# 05_Inputs_28-35.net
KiCad netlist of a schematic drawn in Altium Designer
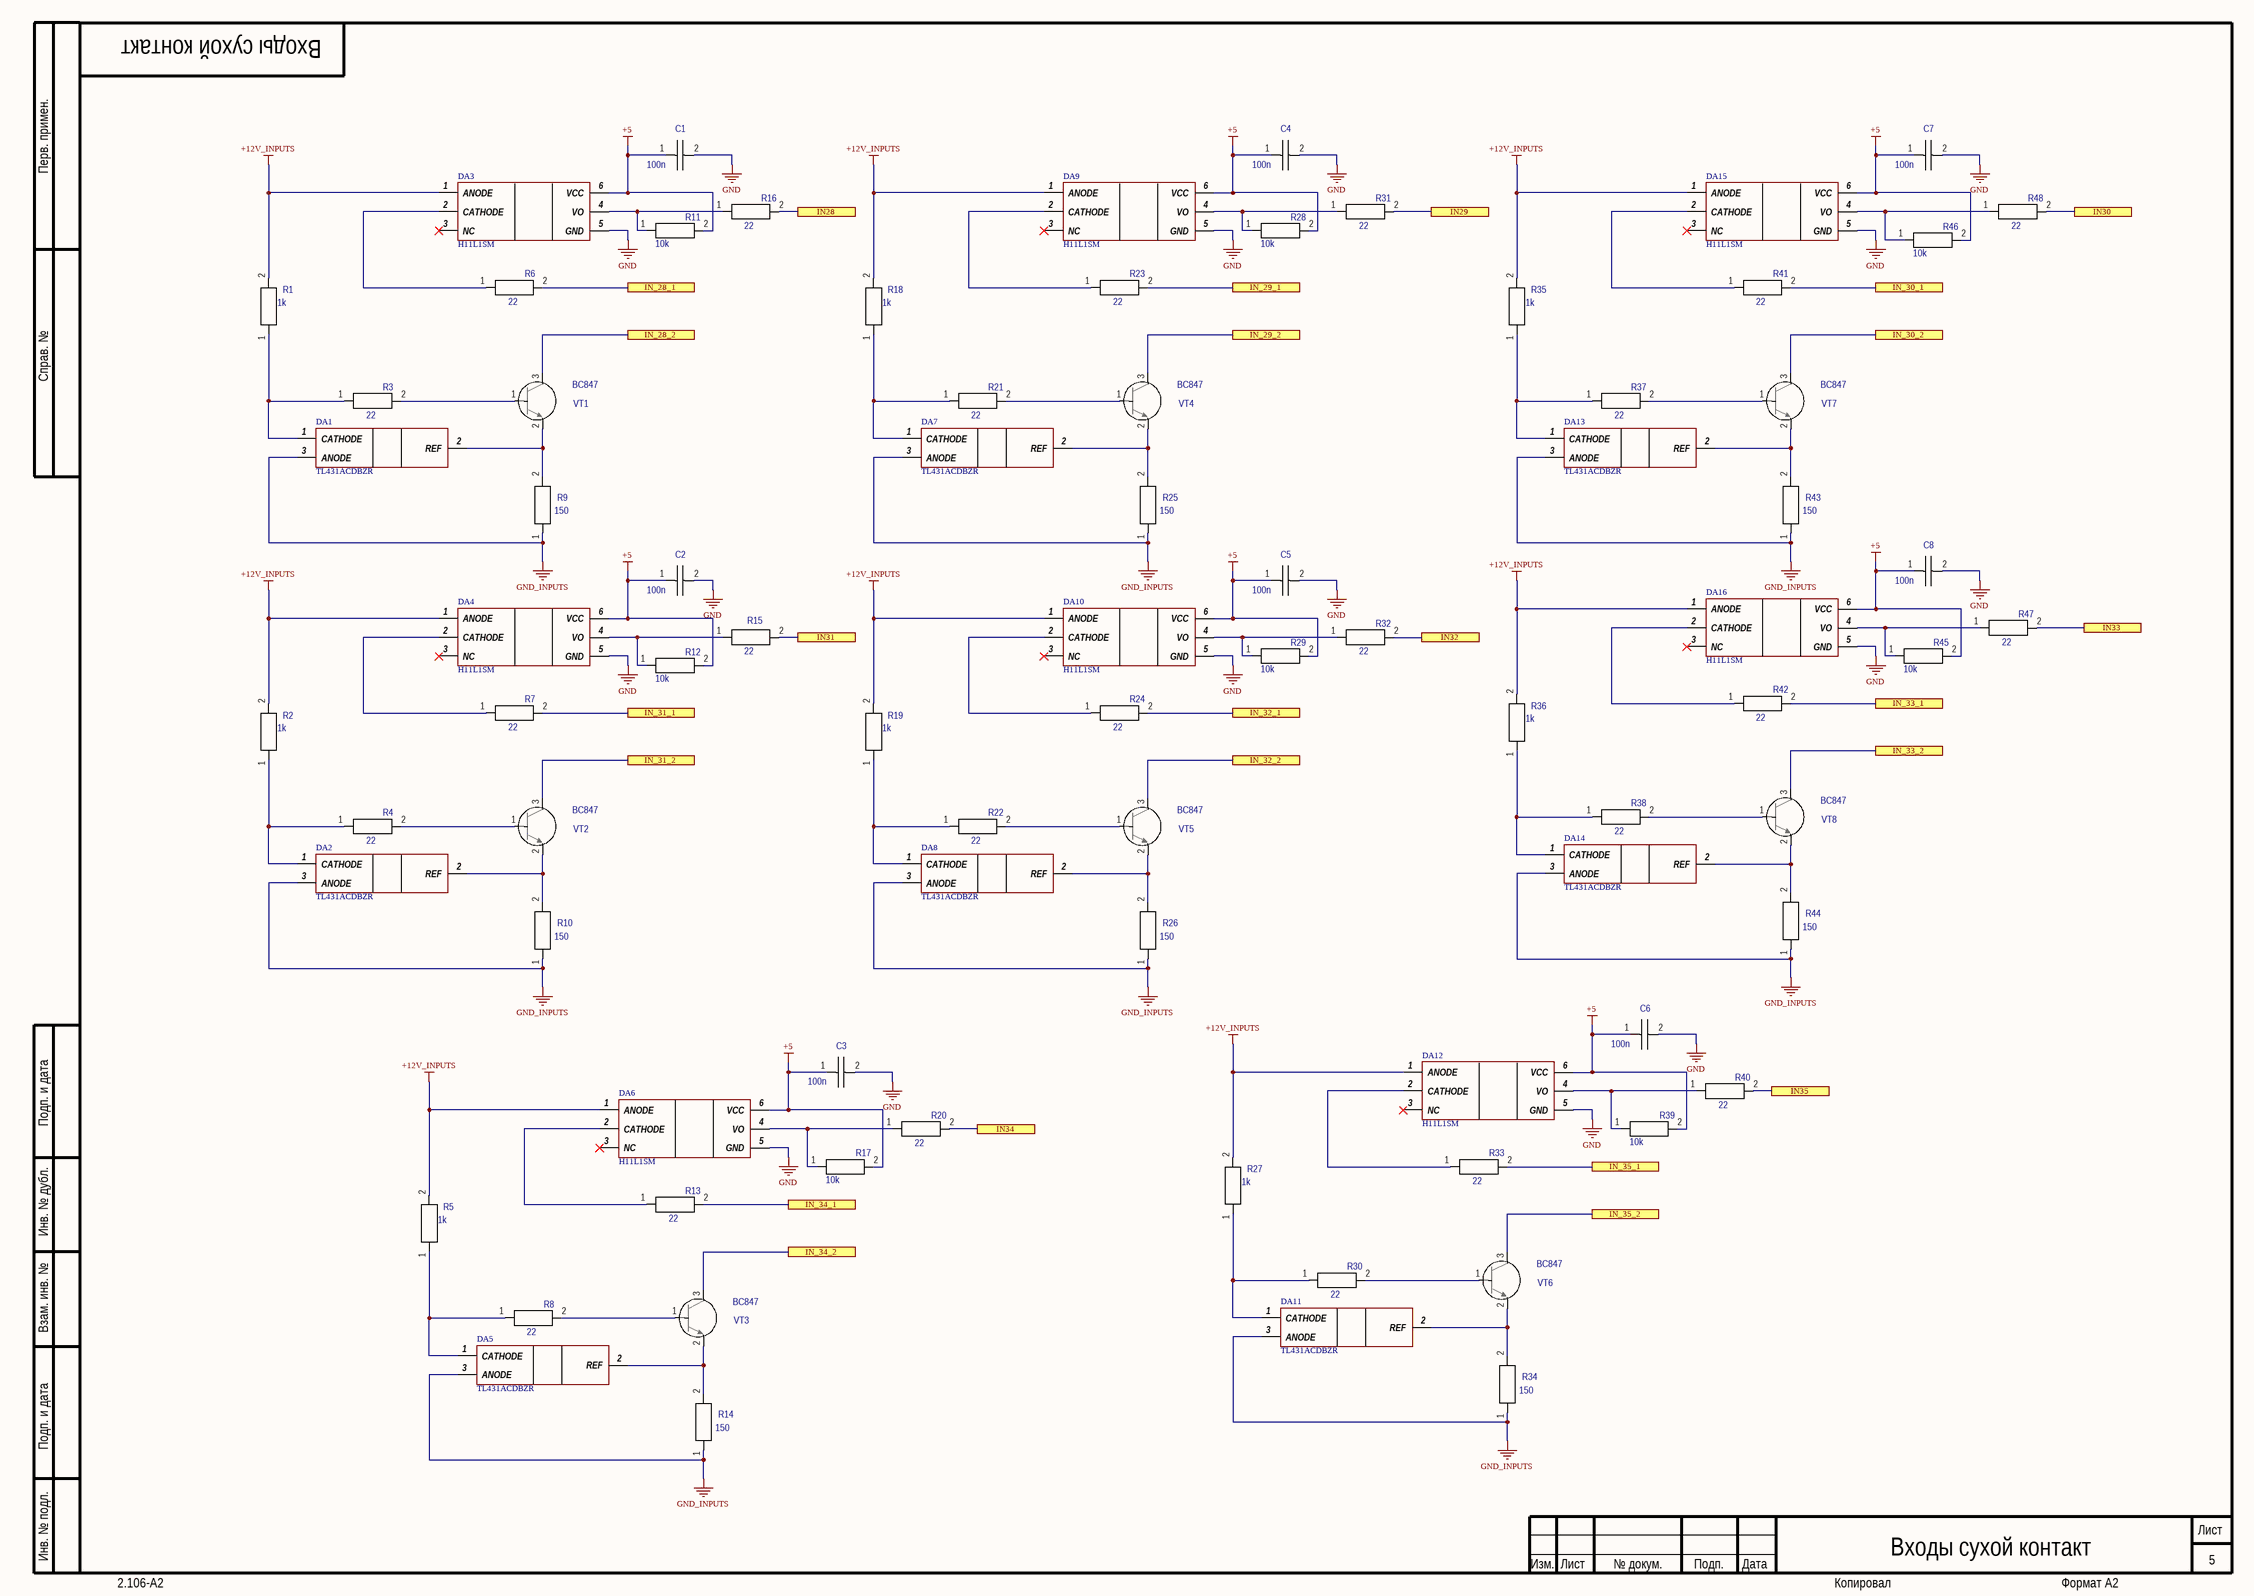
[diagram p0: 05_Inputs_28-35.SchDoc]

(export (version "E")
  (design (tool "Eeschema 10.0.6"))
  (components
    (comp (ref "C1")
      (value "100n")
      (footprint "C0603")
      (fields
        (field (name "PART NUMBER") "GRM188R71C104KA01D")
        (field (name "TOLERANCE") "±10%")
        (field (name "MANUFACTURER") "Murata Manufacturing")
      )
      (libsource (lib "AccessLibrary") (part "Capacitor"))
    )
    (comp (ref "C2")
      (value "100n")
      (footprint "C0603")
      (fields
        (field (name "PART NUMBER") "GRM188R71C104KA01D")
        (field (name "TOLERANCE") "±10%")
        (field (name "MANUFACTURER") "Murata Manufacturing")
      )
      (libsource (lib "AccessLibrary") (part "Capacitor"))
    )
    (comp (ref "C3")
      (value "100n")
      (footprint "C0603")
      (fields
        (field (name "PART NUMBER") "GRM188R71C104KA01D")
        (field (name "TOLERANCE") "±10%")
        (field (name "MANUFACTURER") "Murata Manufacturing")
      )
      (libsource (lib "AccessLibrary") (part "Capacitor"))
    )
    (comp (ref "C4")
      (value "100n")
      (footprint "C0603")
      (fields
        (field (name "PART NUMBER") "GRM188R71C104KA01D")
        (field (name "TOLERANCE") "±10%")
        (field (name "MANUFACTURER") "Murata Manufacturing")
      )
      (libsource (lib "AccessLibrary") (part "Capacitor"))
    )
    (comp (ref "C5")
      (value "100n")
      (footprint "C0603")
      (fields
        (field (name "PART NUMBER") "GRM188R71C104KA01D")
        (field (name "TOLERANCE") "±10%")
        (field (name "MANUFACTURER") "Murata Manufacturing")
      )
      (libsource (lib "AccessLibrary") (part "Capacitor"))
    )
    (comp (ref "C6")
      (value "100n")
      (footprint "C0603")
      (fields
        (field (name "PART NUMBER") "GRM188R71C104KA01D")
        (field (name "TOLERANCE") "±10%")
        (field (name "MANUFACTURER") "Murata Manufacturing")
      )
      (libsource (lib "AccessLibrary") (part "Capacitor"))
    )
    (comp (ref "C7")
      (value "100n")
      (footprint "C0603")
      (fields
        (field (name "PART NUMBER") "GRM188R71C104KA01D")
        (field (name "TOLERANCE") "±10%")
        (field (name "MANUFACTURER") "Murata Manufacturing")
      )
      (libsource (lib "AccessLibrary") (part "Capacitor"))
    )
    (comp (ref "C8")
      (value "100n")
      (footprint "C0603")
      (fields
        (field (name "PART NUMBER") "GRM188R71C104KA01D")
        (field (name "TOLERANCE") "±10%")
        (field (name "MANUFACTURER") "Murata Manufacturing")
      )
      (libsource (lib "AccessLibrary") (part "Capacitor"))
    )
    (comp (ref "DA1")
      (value "TL431ACDBZR")
      (footprint "board:SOT95P237X112-3N")
      (description "Integrated Circuit")
      (fields (field (name "MOUSER PART NUMBER") "595-TL431ACDBZR"))
      (libsource (lib "board") (part "TL431ACDBZR"))
    )
    (comp (ref "DA2")
      (value "TL431ACDBZR")
      (footprint "board:SOT95P237X112-3N")
      (description "Integrated Circuit")
      (fields (field (name "MOUSER PART NUMBER") "595-TL431ACDBZR"))
      (libsource (lib "board") (part "TL431ACDBZR"))
    )
    (comp (ref "DA3")
      (value "H11L1SM")
      (footprint "board:SOP254P1030X460-6N")
      (description "Integrated Circuit")
      (libsource (lib "board") (part "H11L1SM"))
    )
    (comp (ref "DA4")
      (value "H11L1SM")
      (footprint "board:SOP254P1030X460-6N")
      (description "Integrated Circuit")
      (libsource (lib "board") (part "H11L1SM"))
    )
    (comp (ref "DA5")
      (value "TL431ACDBZR")
      (footprint "board:SOT95P237X112-3N")
      (description "Integrated Circuit")
      (fields (field (name "MOUSER PART NUMBER") "595-TL431ACDBZR"))
      (libsource (lib "board") (part "TL431ACDBZR"))
    )
    (comp (ref "DA6")
      (value "H11L1SM")
      (footprint "board:SOP254P1030X460-6N")
      (description "Integrated Circuit")
      (libsource (lib "board") (part "H11L1SM"))
    )
    (comp (ref "DA7")
      (value "TL431ACDBZR")
      (footprint "board:SOT95P237X112-3N")
      (description "Integrated Circuit")
      (fields (field (name "MOUSER PART NUMBER") "595-TL431ACDBZR"))
      (libsource (lib "board") (part "TL431ACDBZR"))
    )
    (comp (ref "DA8")
      (value "TL431ACDBZR")
      (footprint "board:SOT95P237X112-3N")
      (description "Integrated Circuit")
      (fields (field (name "MOUSER PART NUMBER") "595-TL431ACDBZR"))
      (libsource (lib "board") (part "TL431ACDBZR"))
    )
    (comp (ref "DA9")
      (value "H11L1SM")
      (footprint "board:SOP254P1030X460-6N")
      (description "Integrated Circuit")
      (libsource (lib "board") (part "H11L1SM"))
    )
    (comp (ref "DA10")
      (value "H11L1SM")
      (footprint "board:SOP254P1030X460-6N")
      (description "Integrated Circuit")
      (libsource (lib "board") (part "H11L1SM"))
    )
    (comp (ref "DA11")
      (value "TL431ACDBZR")
      (footprint "board:SOT95P237X112-3N")
      (description "Integrated Circuit")
      (fields (field (name "MOUSER PART NUMBER") "595-TL431ACDBZR"))
      (libsource (lib "board") (part "TL431ACDBZR"))
    )
    (comp (ref "DA12")
      (value "H11L1SM")
      (footprint "board:SOP254P1030X460-6N")
      (description "Integrated Circuit")
      (libsource (lib "board") (part "H11L1SM"))
    )
    (comp (ref "DA13")
      (value "TL431ACDBZR")
      (footprint "board:SOT95P237X112-3N")
      (description "Integrated Circuit")
      (fields (field (name "MOUSER PART NUMBER") "595-TL431ACDBZR"))
      (libsource (lib "board") (part "TL431ACDBZR"))
    )
    (comp (ref "DA14")
      (value "TL431ACDBZR")
      (footprint "board:SOT95P237X112-3N")
      (description "Integrated Circuit")
      (fields (field (name "MOUSER PART NUMBER") "595-TL431ACDBZR"))
      (libsource (lib "board") (part "TL431ACDBZR"))
    )
    (comp (ref "DA15")
      (value "H11L1SM")
      (footprint "board:SOP254P1030X460-6N")
      (description "Integrated Circuit")
      (libsource (lib "board") (part "H11L1SM"))
    )
    (comp (ref "DA16")
      (value "H11L1SM")
      (footprint "board:SOP254P1030X460-6N")
      (description "Integrated Circuit")
      (libsource (lib "board") (part "H11L1SM"))
    )
    (comp (ref "R1")
      (value "1k")
      (footprint "RESC1608N")
      (fields
        (field (name "PART NUMBER") "RC0603FK-071KL")
        (field (name "TOLERANCE") "±1%")
        (field (name "MANUFACTURER") "Тайвань")
      )
      (libsource (lib "AccessLibrary") (part "Resistor"))
    )
    (comp (ref "R2")
      (value "1k")
      (footprint "RESC1608N")
      (fields
        (field (name "PART NUMBER") "RC0603FK-071KL")
        (field (name "TOLERANCE") "±1%")
        (field (name "MANUFACTURER") "Тайвань")
      )
      (libsource (lib "AccessLibrary") (part "Resistor"))
    )
    (comp (ref "R3")
      (value "22")
      (footprint "RESC1608N")
      (fields
        (field (name "PART NUMBER") "RC0603FK-0722RL")
        (field (name "TOLERANCE") "±1%")
        (field (name "MANUFACTURER") "Тайвань")
      )
      (libsource (lib "AccessLibrary") (part "Resistor"))
    )
    (comp (ref "R4")
      (value "22")
      (footprint "RESC1608N")
      (fields
        (field (name "PART NUMBER") "RC0603FK-0722RL")
        (field (name "TOLERANCE") "±1%")
        (field (name "MANUFACTURER") "Тайвань")
      )
      (libsource (lib "AccessLibrary") (part "Resistor"))
    )
    (comp (ref "R5")
      (value "1k")
      (footprint "RESC1608N")
      (fields
        (field (name "PART NUMBER") "RC0603FK-071KL")
        (field (name "TOLERANCE") "±1%")
        (field (name "MANUFACTURER") "Тайвань")
      )
      (libsource (lib "AccessLibrary") (part "Resistor"))
    )
    (comp (ref "R6")
      (value "22")
      (footprint "RESC1608N")
      (fields
        (field (name "PART NUMBER") "RC0603FK-0722RL")
        (field (name "TOLERANCE") "±1%")
        (field (name "MANUFACTURER") "Тайвань")
      )
      (libsource (lib "AccessLibrary") (part "Resistor"))
    )
    (comp (ref "R7")
      (value "22")
      (footprint "RESC1608N")
      (fields
        (field (name "PART NUMBER") "RC0603FK-0722RL")
        (field (name "TOLERANCE") "±1%")
        (field (name "MANUFACTURER") "Тайвань")
      )
      (libsource (lib "AccessLibrary") (part "Resistor"))
    )
    (comp (ref "R8")
      (value "22")
      (footprint "RESC1608N")
      (fields
        (field (name "PART NUMBER") "RC0603FK-0722RL")
        (field (name "TOLERANCE") "±1%")
        (field (name "MANUFACTURER") "Тайвань")
      )
      (libsource (lib "AccessLibrary") (part "Resistor"))
    )
    (comp (ref "R9")
      (value "150")
      (footprint "RESC1608N")
      (fields
        (field (name "PART NUMBER") "RC0603FK-07150RL")
        (field (name "TOLERANCE") "±1%")
        (field (name "MANUFACTURER") "Тайвань")
      )
      (libsource (lib "AccessLibrary") (part "Resistor"))
    )
    (comp (ref "R10")
      (value "150")
      (footprint "RESC1608N")
      (fields
        (field (name "PART NUMBER") "RC0603FK-07150RL")
        (field (name "TOLERANCE") "±1%")
        (field (name "MANUFACTURER") "Тайвань")
      )
      (libsource (lib "AccessLibrary") (part "Resistor"))
    )
    (comp (ref "R11")
      (value "10k")
      (footprint "RESC1608N")
      (fields
        (field (name "PART NUMBER") "RC0603FR-0710KL")
        (field (name "TOLERANCE") "±1%")
        (field (name "MANUFACTURER") "Тайвань")
      )
      (libsource (lib "AccessLibrary") (part "Resistor"))
    )
    (comp (ref "R12")
      (value "10k")
      (footprint "RESC1608N")
      (fields
        (field (name "PART NUMBER") "RC0603FR-0710KL")
        (field (name "TOLERANCE") "±1%")
        (field (name "MANUFACTURER") "Тайвань")
      )
      (libsource (lib "AccessLibrary") (part "Resistor"))
    )
    (comp (ref "R13")
      (value "22")
      (footprint "RESC1608N")
      (fields
        (field (name "PART NUMBER") "RC0603FK-0722RL")
        (field (name "TOLERANCE") "±1%")
        (field (name "MANUFACTURER") "Тайвань")
      )
      (libsource (lib "AccessLibrary") (part "Resistor"))
    )
    (comp (ref "R14")
      (value "150")
      (footprint "RESC1608N")
      (fields
        (field (name "PART NUMBER") "RC0603FK-07150RL")
        (field (name "TOLERANCE") "±1%")
        (field (name "MANUFACTURER") "Тайвань")
      )
      (libsource (lib "AccessLibrary") (part "Resistor"))
    )
    (comp (ref "R15")
      (value "22")
      (footprint "RESC1608N")
      (fields
        (field (name "PART NUMBER") "RC0603FK-0722RL")
        (field (name "TOLERANCE") "±1%")
        (field (name "MANUFACTURER") "Тайвань")
      )
      (libsource (lib "AccessLibrary") (part "Resistor"))
    )
    (comp (ref "R16")
      (value "22")
      (footprint "RESC1608N")
      (fields
        (field (name "PART NUMBER") "RC0603FK-0722RL")
        (field (name "TOLERANCE") "±1%")
        (field (name "MANUFACTURER") "Тайвань")
      )
      (libsource (lib "AccessLibrary") (part "Resistor"))
    )
    (comp (ref "R17")
      (value "10k")
      (footprint "RESC1608N")
      (fields
        (field (name "PART NUMBER") "RC0603FR-0710KL")
        (field (name "TOLERANCE") "±1%")
        (field (name "MANUFACTURER") "Тайвань")
      )
      (libsource (lib "AccessLibrary") (part "Resistor"))
    )
    (comp (ref "R18")
      (value "1k")
      (footprint "RESC1608N")
      (fields
        (field (name "PART NUMBER") "RC0603FK-071KL")
        (field (name "TOLERANCE") "±1%")
        (field (name "MANUFACTURER") "Тайвань")
      )
      (libsource (lib "AccessLibrary") (part "Resistor"))
    )
    (comp (ref "R19")
      (value "1k")
      (footprint "RESC1608N")
      (fields
        (field (name "PART NUMBER") "RC0603FK-071KL")
        (field (name "TOLERANCE") "±1%")
        (field (name "MANUFACTURER") "Тайвань")
      )
      (libsource (lib "AccessLibrary") (part "Resistor"))
    )
    (comp (ref "R20")
      (value "22")
      (footprint "RESC1608N")
      (fields
        (field (name "PART NUMBER") "RC0603FK-0722RL")
        (field (name "TOLERANCE") "±1%")
        (field (name "MANUFACTURER") "Тайвань")
      )
      (libsource (lib "AccessLibrary") (part "Resistor"))
    )
    (comp (ref "R21")
      (value "22")
      (footprint "RESC1608N")
      (fields
        (field (name "PART NUMBER") "RC0603FK-0722RL")
        (field (name "TOLERANCE") "±1%")
        (field (name "MANUFACTURER") "Тайвань")
      )
      (libsource (lib "AccessLibrary") (part "Resistor"))
    )
    (comp (ref "R22")
      (value "22")
      (footprint "RESC1608N")
      (fields
        (field (name "PART NUMBER") "RC0603FK-0722RL")
        (field (name "TOLERANCE") "±1%")
        (field (name "MANUFACTURER") "Тайвань")
      )
      (libsource (lib "AccessLibrary") (part "Resistor"))
    )
    (comp (ref "R23")
      (value "22")
      (footprint "RESC1608N")
      (fields
        (field (name "PART NUMBER") "RC0603FK-0722RL")
        (field (name "TOLERANCE") "±1%")
        (field (name "MANUFACTURER") "Тайвань")
      )
      (libsource (lib "AccessLibrary") (part "Resistor"))
    )
    (comp (ref "R24")
      (value "22")
      (footprint "RESC1608N")
      (fields
        (field (name "PART NUMBER") "RC0603FK-0722RL")
        (field (name "TOLERANCE") "±1%")
        (field (name "MANUFACTURER") "Тайвань")
      )
      (libsource (lib "AccessLibrary") (part "Resistor"))
    )
    (comp (ref "R25")
      (value "150")
      (footprint "RESC1608N")
      (fields
        (field (name "PART NUMBER") "RC0603FK-07150RL")
        (field (name "TOLERANCE") "±1%")
        (field (name "MANUFACTURER") "Тайвань")
      )
      (libsource (lib "AccessLibrary") (part "Resistor"))
    )
    (comp (ref "R26")
      (value "150")
      (footprint "RESC1608N")
      (fields
        (field (name "PART NUMBER") "RC0603FK-07150RL")
        (field (name "TOLERANCE") "±1%")
        (field (name "MANUFACTURER") "Тайвань")
      )
      (libsource (lib "AccessLibrary") (part "Resistor"))
    )
    (comp (ref "R27")
      (value "1k")
      (footprint "RESC1608N")
      (fields
        (field (name "PART NUMBER") "RC0603FK-071KL")
        (field (name "TOLERANCE") "±1%")
        (field (name "MANUFACTURER") "Тайвань")
      )
      (libsource (lib "AccessLibrary") (part "Resistor"))
    )
    (comp (ref "R28")
      (value "10k")
      (footprint "RESC1608N")
      (fields
        (field (name "PART NUMBER") "RC0603FR-0710KL")
        (field (name "TOLERANCE") "±1%")
        (field (name "MANUFACTURER") "Тайвань")
      )
      (libsource (lib "AccessLibrary") (part "Resistor"))
    )
    (comp (ref "R29")
      (value "10k")
      (footprint "RESC1608N")
      (fields
        (field (name "PART NUMBER") "RC0603FR-0710KL")
        (field (name "TOLERANCE") "±1%")
        (field (name "MANUFACTURER") "Тайвань")
      )
      (libsource (lib "AccessLibrary") (part "Resistor"))
    )
    (comp (ref "R30")
      (value "22")
      (footprint "RESC1608N")
      (fields
        (field (name "PART NUMBER") "RC0603FK-0722RL")
        (field (name "TOLERANCE") "±1%")
        (field (name "MANUFACTURER") "Тайвань")
      )
      (libsource (lib "AccessLibrary") (part "Resistor"))
    )
    (comp (ref "R31")
      (value "22")
      (footprint "RESC1608N")
      (fields
        (field (name "PART NUMBER") "RC0603FK-0722RL")
        (field (name "TOLERANCE") "±1%")
        (field (name "MANUFACTURER") "Тайвань")
      )
      (libsource (lib "AccessLibrary") (part "Resistor"))
    )
    (comp (ref "R32")
      (value "22")
      (footprint "RESC1608N")
      (fields
        (field (name "PART NUMBER") "RC0603FK-0722RL")
        (field (name "TOLERANCE") "±1%")
        (field (name "MANUFACTURER") "Тайвань")
      )
      (libsource (lib "AccessLibrary") (part "Resistor"))
    )
    (comp (ref "R33")
      (value "22")
      (footprint "RESC1608N")
      (fields
        (field (name "PART NUMBER") "RC0603FK-0722RL")
        (field (name "TOLERANCE") "±1%")
        (field (name "MANUFACTURER") "Тайвань")
      )
      (libsource (lib "AccessLibrary") (part "Resistor"))
    )
    (comp (ref "R34")
      (value "150")
      (footprint "RESC1608N")
      (fields
        (field (name "PART NUMBER") "RC0603FK-07150RL")
        (field (name "TOLERANCE") "±1%")
        (field (name "MANUFACTURER") "Тайвань")
      )
      (libsource (lib "AccessLibrary") (part "Resistor"))
    )
    (comp (ref "R35")
      (value "1k")
      (footprint "RESC1608N")
      (fields
        (field (name "PART NUMBER") "RC0603FK-071KL")
        (field (name "TOLERANCE") "±1%")
        (field (name "MANUFACTURER") "Тайвань")
      )
      (libsource (lib "AccessLibrary") (part "Resistor"))
    )
    (comp (ref "R36")
      (value "1k")
      (footprint "RESC1608N")
      (fields
        (field (name "PART NUMBER") "RC0603FK-071KL")
        (field (name "TOLERANCE") "±1%")
        (field (name "MANUFACTURER") "Тайвань")
      )
      (libsource (lib "AccessLibrary") (part "Resistor"))
    )
    (comp (ref "R37")
      (value "22")
      (footprint "RESC1608N")
      (fields
        (field (name "PART NUMBER") "RC0603FK-0722RL")
        (field (name "TOLERANCE") "±1%")
        (field (name "MANUFACTURER") "Тайвань")
      )
      (libsource (lib "AccessLibrary") (part "Resistor"))
    )
    (comp (ref "R38")
      (value "22")
      (footprint "RESC1608N")
      (fields
        (field (name "PART NUMBER") "RC0603FK-0722RL")
        (field (name "TOLERANCE") "±1%")
        (field (name "MANUFACTURER") "Тайвань")
      )
      (libsource (lib "AccessLibrary") (part "Resistor"))
    )
    (comp (ref "R39")
      (value "10k")
      (footprint "RESC1608N")
      (fields
        (field (name "PART NUMBER") "RC0603FR-0710KL")
        (field (name "TOLERANCE") "±1%")
        (field (name "MANUFACTURER") "Тайвань")
      )
      (libsource (lib "AccessLibrary") (part "Resistor"))
    )
    (comp (ref "R40")
      (value "22")
      (footprint "RESC1608N")
      (fields
        (field (name "PART NUMBER") "RC0603FK-0722RL")
        (field (name "TOLERANCE") "±1%")
        (field (name "MANUFACTURER") "Тайвань")
      )
      (libsource (lib "AccessLibrary") (part "Resistor"))
    )
    (comp (ref "R41")
      (value "22")
      (footprint "RESC1608N")
      (fields
        (field (name "PART NUMBER") "RC0603FK-0722RL")
        (field (name "TOLERANCE") "±1%")
        (field (name "MANUFACTURER") "Тайвань")
      )
      (libsource (lib "AccessLibrary") (part "Resistor"))
    )
    (comp (ref "R42")
      (value "22")
      (footprint "RESC1608N")
      (fields
        (field (name "PART NUMBER") "RC0603FK-0722RL")
        (field (name "TOLERANCE") "±1%")
        (field (name "MANUFACTURER") "Тайвань")
      )
      (libsource (lib "AccessLibrary") (part "Resistor"))
    )
    (comp (ref "R43")
      (value "150")
      (footprint "RESC1608N")
      (fields
        (field (name "PART NUMBER") "RC0603FK-07150RL")
        (field (name "TOLERANCE") "±1%")
        (field (name "MANUFACTURER") "Тайвань")
      )
      (libsource (lib "AccessLibrary") (part "Resistor"))
    )
    (comp (ref "R44")
      (value "150")
      (footprint "RESC1608N")
      (fields
        (field (name "PART NUMBER") "RC0603FK-07150RL")
        (field (name "TOLERANCE") "±1%")
        (field (name "MANUFACTURER") "Тайвань")
      )
      (libsource (lib "AccessLibrary") (part "Resistor"))
    )
    (comp (ref "R45")
      (value "10k")
      (footprint "RESC1608N")
      (fields
        (field (name "PART NUMBER") "RC0603FR-0710KL")
        (field (name "TOLERANCE") "±1%")
        (field (name "MANUFACTURER") "Тайвань")
      )
      (libsource (lib "AccessLibrary") (part "Resistor"))
    )
    (comp (ref "R46")
      (value "10k")
      (footprint "RESC1608N")
      (fields
        (field (name "PART NUMBER") "RC0603FR-0710KL")
        (field (name "TOLERANCE") "±1%")
        (field (name "MANUFACTURER") "Тайвань")
      )
      (libsource (lib "AccessLibrary") (part "Resistor"))
    )
    (comp (ref "R47")
      (value "22")
      (footprint "RESC1608N")
      (fields
        (field (name "PART NUMBER") "RC0603FK-0722RL")
        (field (name "TOLERANCE") "±1%")
        (field (name "MANUFACTURER") "Тайвань")
      )
      (libsource (lib "AccessLibrary") (part "Resistor"))
    )
    (comp (ref "R48")
      (value "22")
      (footprint "RESC1608N")
      (fields
        (field (name "PART NUMBER") "RC0603FK-0722RL")
        (field (name "TOLERANCE") "±1%")
        (field (name "MANUFACTURER") "Тайвань")
      )
      (libsource (lib "AccessLibrary") (part "Resistor"))
    )
    (comp (ref "VT1")
      (value "BC847")
      (footprint "SOT23-3N")
      (fields (field (name "COM") "BC847") (field (name "MANUFACTURER") "NXP Semiconductor"))
      (libsource (lib "AccessLibrary") (part "Transistor_npn_1b-2e-3c"))
    )
    (comp (ref "VT2")
      (value "BC847")
      (footprint "SOT23-3N")
      (fields (field (name "COM") "BC847") (field (name "MANUFACTURER") "NXP Semiconductor"))
      (libsource (lib "AccessLibrary") (part "Transistor_npn_1b-2e-3c"))
    )
    (comp (ref "VT3")
      (value "BC847")
      (footprint "SOT23-3N")
      (fields (field (name "COM") "BC847") (field (name "MANUFACTURER") "NXP Semiconductor"))
      (libsource (lib "AccessLibrary") (part "Transistor_npn_1b-2e-3c"))
    )
    (comp (ref "VT4")
      (value "BC847")
      (footprint "SOT23-3N")
      (fields (field (name "COM") "BC847") (field (name "MANUFACTURER") "NXP Semiconductor"))
      (libsource (lib "AccessLibrary") (part "Transistor_npn_1b-2e-3c"))
    )
    (comp (ref "VT5")
      (value "BC847")
      (footprint "SOT23-3N")
      (fields (field (name "COM") "BC847") (field (name "MANUFACTURER") "NXP Semiconductor"))
      (libsource (lib "AccessLibrary") (part "Transistor_npn_1b-2e-3c"))
    )
    (comp (ref "VT6")
      (value "BC847")
      (footprint "SOT23-3N")
      (fields (field (name "COM") "BC847") (field (name "MANUFACTURER") "NXP Semiconductor"))
      (libsource (lib "AccessLibrary") (part "Transistor_npn_1b-2e-3c"))
    )
    (comp (ref "VT7")
      (value "BC847")
      (footprint "SOT23-3N")
      (fields (field (name "COM") "BC847") (field (name "MANUFACTURER") "NXP Semiconductor"))
      (libsource (lib "AccessLibrary") (part "Transistor_npn_1b-2e-3c"))
    )
    (comp (ref "VT8")
      (value "BC847")
      (footprint "SOT23-3N")
      (fields (field (name "COM") "BC847") (field (name "MANUFACTURER") "NXP Semiconductor"))
      (libsource (lib "AccessLibrary") (part "Transistor_npn_1b-2e-3c"))
    )
  )
  (nets
    (net (code "1") (name "+5") (class "Default")
      (node (ref "C1") (pin "1") (pinfunction "1_1") (pintype "passive"))
      (node (ref "C2") (pin "1") (pinfunction "1_1") (pintype "passive"))
      (node (ref "C3") (pin "1") (pinfunction "1_1") (pintype "passive"))
      (node (ref "C4") (pin "1") (pinfunction "1_1") (pintype "passive"))
      (node (ref "C5") (pin "1") (pinfunction "1_1") (pintype "passive"))
      (node (ref "C6") (pin "1") (pinfunction "1_1") (pintype "passive"))
      (node (ref "C7") (pin "1") (pinfunction "1_1") (pintype "passive"))
      (node (ref "C8") (pin "1") (pinfunction "1_1") (pintype "passive"))
      (node (ref "DA10") (pin "6") (pinfunction "VCC_6") (pintype "passive"))
      (node (ref "DA12") (pin "6") (pinfunction "VCC_6") (pintype "passive"))
      (node (ref "DA15") (pin "6") (pinfunction "VCC_6") (pintype "passive"))
      (node (ref "DA16") (pin "6") (pinfunction "VCC_6") (pintype "passive"))
      (node (ref "DA3") (pin "6") (pinfunction "VCC_6") (pintype "passive"))
      (node (ref "DA4") (pin "6") (pinfunction "VCC_6") (pintype "passive"))
      (node (ref "DA6") (pin "6") (pinfunction "VCC_6") (pintype "passive"))
      (node (ref "DA9") (pin "6") (pinfunction "VCC_6") (pintype "passive"))
      (node (ref "R11") (pin "2") (pinfunction "2_2") (pintype "passive"))
      (node (ref "R12") (pin "2") (pinfunction "2_2") (pintype "passive"))
      (node (ref "R17") (pin "2") (pinfunction "2_2") (pintype "passive"))
      (node (ref "R28") (pin "2") (pinfunction "2_2") (pintype "passive"))
      (node (ref "R29") (pin "2") (pinfunction "2_2") (pintype "passive"))
      (node (ref "R39") (pin "2") (pinfunction "2_2") (pintype "passive"))
      (node (ref "R45") (pin "2") (pinfunction "2_2") (pintype "passive"))
      (node (ref "R46") (pin "2") (pinfunction "2_2") (pintype "passive"))
    )
    (net (code "2") (name "+12V_INPUTS") (class "Default")
      (node (ref "DA10") (pin "1") (pinfunction "ANODE_1") (pintype "passive"))
      (node (ref "DA12") (pin "1") (pinfunction "ANODE_1") (pintype "passive"))
      (node (ref "DA15") (pin "1") (pinfunction "ANODE_1") (pintype "passive"))
      (node (ref "DA16") (pin "1") (pinfunction "ANODE_1") (pintype "passive"))
      (node (ref "DA3") (pin "1") (pinfunction "ANODE_1") (pintype "passive"))
      (node (ref "DA4") (pin "1") (pinfunction "ANODE_1") (pintype "passive"))
      (node (ref "DA6") (pin "1") (pinfunction "ANODE_1") (pintype "passive"))
      (node (ref "DA9") (pin "1") (pinfunction "ANODE_1") (pintype "passive"))
      (node (ref "R1") (pin "2") (pinfunction "2_2") (pintype "passive"))
      (node (ref "R18") (pin "2") (pinfunction "2_2") (pintype "passive"))
      (node (ref "R19") (pin "2") (pinfunction "2_2") (pintype "passive"))
      (node (ref "R2") (pin "2") (pinfunction "2_2") (pintype "passive"))
      (node (ref "R27") (pin "2") (pinfunction "2_2") (pintype "passive"))
      (node (ref "R35") (pin "2") (pinfunction "2_2") (pintype "passive"))
      (node (ref "R36") (pin "2") (pinfunction "2_2") (pintype "passive"))
      (node (ref "R5") (pin "2") (pinfunction "2_2") (pintype "passive"))
    )
    (net (code "3") (name "/IN28") (class "Default")
      (node (ref "R16") (pin "2") (pinfunction "2_2") (pintype "passive"))
    )
    (net (code "4") (name "/IN29") (class "Default")
      (node (ref "R31") (pin "2") (pinfunction "2_2") (pintype "passive"))
    )
    (net (code "5") (name "/IN30") (class "Default")
      (node (ref "R48") (pin "2") (pinfunction "2_2") (pintype "passive"))
    )
    (net (code "6") (name "/IN31") (class "Default")
      (node (ref "R15") (pin "2") (pinfunction "2_2") (pintype "passive"))
    )
    (net (code "7") (name "/IN32") (class "Default")
      (node (ref "R32") (pin "2") (pinfunction "2_2") (pintype "passive"))
    )
    (net (code "8") (name "/IN33") (class "Default")
      (node (ref "R47") (pin "2") (pinfunction "2_2") (pintype "passive"))
    )
    (net (code "9") (name "/IN34") (class "Default")
      (node (ref "R20") (pin "2") (pinfunction "2_2") (pintype "passive"))
    )
    (net (code "10") (name "/IN35") (class "Default")
      (node (ref "R40") (pin "2") (pinfunction "2_2") (pintype "passive"))
    )
    (net (code "11") (name "/IN_28_1") (class "Default")
      (node (ref "R6") (pin "2") (pinfunction "2_2") (pintype "passive"))
    )
    (net (code "12") (name "/IN_28_2") (class "Default")
      (node (ref "VT1") (pin "3") (pinfunction "3_3") (pintype "passive"))
    )
    (net (code "13") (name "/IN_29_1") (class "Default")
      (node (ref "R23") (pin "2") (pinfunction "2_2") (pintype "passive"))
    )
    (net (code "14") (name "/IN_29_2") (class "Default")
      (node (ref "VT4") (pin "3") (pinfunction "3_3") (pintype "passive"))
    )
    (net (code "15") (name "/IN_30_1") (class "Default")
      (node (ref "R41") (pin "2") (pinfunction "2_2") (pintype "passive"))
    )
    (net (code "16") (name "/IN_30_2") (class "Default")
      (node (ref "VT7") (pin "3") (pinfunction "3_3") (pintype "passive"))
    )
    (net (code "17") (name "/IN_31_1") (class "Default")
      (node (ref "R7") (pin "2") (pinfunction "2_2") (pintype "passive"))
    )
    (net (code "18") (name "/IN_31_2") (class "Default")
      (node (ref "VT2") (pin "3") (pinfunction "3_3") (pintype "passive"))
    )
    (net (code "19") (name "/IN_32_1") (class "Default")
      (node (ref "R24") (pin "2") (pinfunction "2_2") (pintype "passive"))
    )
    (net (code "20") (name "/IN_32_2") (class "Default")
      (node (ref "VT5") (pin "3") (pinfunction "3_3") (pintype "passive"))
    )
    (net (code "21") (name "/IN_33_1") (class "Default")
      (node (ref "R42") (pin "2") (pinfunction "2_2") (pintype "passive"))
    )
    (net (code "22") (name "/IN_33_2") (class "Default")
      (node (ref "VT8") (pin "3") (pinfunction "3_3") (pintype "passive"))
    )
    (net (code "23") (name "/IN_34_1") (class "Default")
      (node (ref "R13") (pin "2") (pinfunction "2_2") (pintype "passive"))
    )
    (net (code "24") (name "/IN_34_2") (class "Default")
      (node (ref "VT3") (pin "3") (pinfunction "3_3") (pintype "passive"))
    )
    (net (code "25") (name "/IN_35_1") (class "Default")
      (node (ref "R33") (pin "2") (pinfunction "2_2") (pintype "passive"))
    )
    (net (code "26") (name "/IN_35_2") (class "Default")
      (node (ref "VT6") (pin "3") (pinfunction "3_3") (pintype "passive"))
    )
    (net (code "27") (name "GND") (class "Default")
      (node (ref "C1") (pin "2") (pinfunction "2_2") (pintype "passive"))
      (node (ref "C2") (pin "2") (pinfunction "2_2") (pintype "passive"))
      (node (ref "C3") (pin "2") (pinfunction "2_2") (pintype "passive"))
      (node (ref "C4") (pin "2") (pinfunction "2_2") (pintype "passive"))
      (node (ref "C5") (pin "2") (pinfunction "2_2") (pintype "passive"))
      (node (ref "C6") (pin "2") (pinfunction "2_2") (pintype "passive"))
      (node (ref "C7") (pin "2") (pinfunction "2_2") (pintype "passive"))
      (node (ref "C8") (pin "2") (pinfunction "2_2") (pintype "passive"))
      (node (ref "DA10") (pin "5") (pinfunction "GND_5") (pintype "passive"))
      (node (ref "DA12") (pin "5") (pinfunction "GND_5") (pintype "passive"))
      (node (ref "DA15") (pin "5") (pinfunction "GND_5") (pintype "passive"))
      (node (ref "DA16") (pin "5") (pinfunction "GND_5") (pintype "passive"))
      (node (ref "DA3") (pin "5") (pinfunction "GND_5") (pintype "passive"))
      (node (ref "DA4") (pin "5") (pinfunction "GND_5") (pintype "passive"))
      (node (ref "DA6") (pin "5") (pinfunction "GND_5") (pintype "passive"))
      (node (ref "DA9") (pin "5") (pinfunction "GND_5") (pintype "passive"))
    )
    (net (code "28") (name "GND_INPUTS") (class "Default")
      (node (ref "DA1") (pin "3") (pinfunction "ANODE_3") (pintype "passive"))
      (node (ref "DA11") (pin "3") (pinfunction "ANODE_3") (pintype "passive"))
      (node (ref "DA13") (pin "3") (pinfunction "ANODE_3") (pintype "passive"))
      (node (ref "DA14") (pin "3") (pinfunction "ANODE_3") (pintype "passive"))
      (node (ref "DA2") (pin "3") (pinfunction "ANODE_3") (pintype "passive"))
      (node (ref "DA5") (pin "3") (pinfunction "ANODE_3") (pintype "passive"))
      (node (ref "DA7") (pin "3") (pinfunction "ANODE_3") (pintype "passive"))
      (node (ref "DA8") (pin "3") (pinfunction "ANODE_3") (pintype "passive"))
      (node (ref "R10") (pin "1") (pinfunction "1_1") (pintype "passive"))
      (node (ref "R14") (pin "1") (pinfunction "1_1") (pintype "passive"))
      (node (ref "R25") (pin "1") (pinfunction "1_1") (pintype "passive"))
      (node (ref "R26") (pin "1") (pinfunction "1_1") (pintype "passive"))
      (node (ref "R34") (pin "1") (pinfunction "1_1") (pintype "passive"))
      (node (ref "R43") (pin "1") (pinfunction "1_1") (pintype "passive"))
      (node (ref "R44") (pin "1") (pinfunction "1_1") (pintype "passive"))
      (node (ref "R9") (pin "1") (pinfunction "1_1") (pintype "passive"))
    )
    (net (code "29") (name "Net-(DA1-CATHODE)") (class "Default")
      (node (ref "DA1") (pin "1") (pinfunction "CATHODE_1") (pintype "passive"))
      (node (ref "R1") (pin "1") (pinfunction "1_1") (pintype "passive"))
      (node (ref "R3") (pin "1") (pinfunction "1_1") (pintype "passive"))
    )
    (net (code "30") (name "Net-(DA1-REF)") (class "Default")
      (node (ref "DA1") (pin "2") (pinfunction "REF_2") (pintype "passive"))
      (node (ref "R9") (pin "2") (pinfunction "2_2") (pintype "passive"))
      (node (ref "VT1") (pin "2") (pinfunction "2_2") (pintype "passive"))
    )
    (net (code "31") (name "Net-(DA2-CATHODE)") (class "Default")
      (node (ref "DA2") (pin "1") (pinfunction "CATHODE_1") (pintype "passive"))
      (node (ref "R2") (pin "1") (pinfunction "1_1") (pintype "passive"))
      (node (ref "R4") (pin "1") (pinfunction "1_1") (pintype "passive"))
    )
    (net (code "32") (name "Net-(DA2-REF)") (class "Default")
      (node (ref "DA2") (pin "2") (pinfunction "REF_2") (pintype "passive"))
      (node (ref "R10") (pin "2") (pinfunction "2_2") (pintype "passive"))
      (node (ref "VT2") (pin "2") (pinfunction "2_2") (pintype "passive"))
    )
    (net (code "33") (name "Net-(DA3-CATHODE)") (class "Default")
      (node (ref "DA3") (pin "2") (pinfunction "CATHODE_2") (pintype "passive"))
      (node (ref "R6") (pin "1") (pinfunction "1_1") (pintype "passive"))
    )
    (net (code "34") (name "Net-(DA3-VO)") (class "Default")
      (node (ref "DA3") (pin "4") (pinfunction "VO_4") (pintype "passive"))
      (node (ref "R11") (pin "1") (pinfunction "1_1") (pintype "passive"))
      (node (ref "R16") (pin "1") (pinfunction "1_1") (pintype "passive"))
    )
    (net (code "35") (name "Net-(DA4-CATHODE)") (class "Default")
      (node (ref "DA4") (pin "2") (pinfunction "CATHODE_2") (pintype "passive"))
      (node (ref "R7") (pin "1") (pinfunction "1_1") (pintype "passive"))
    )
    (net (code "36") (name "Net-(DA4-VO)") (class "Default")
      (node (ref "DA4") (pin "4") (pinfunction "VO_4") (pintype "passive"))
      (node (ref "R12") (pin "1") (pinfunction "1_1") (pintype "passive"))
      (node (ref "R15") (pin "1") (pinfunction "1_1") (pintype "passive"))
    )
    (net (code "37") (name "Net-(DA5-CATHODE)") (class "Default")
      (node (ref "DA5") (pin "1") (pinfunction "CATHODE_1") (pintype "passive"))
      (node (ref "R5") (pin "1") (pinfunction "1_1") (pintype "passive"))
      (node (ref "R8") (pin "1") (pinfunction "1_1") (pintype "passive"))
    )
    (net (code "38") (name "Net-(DA5-REF)") (class "Default")
      (node (ref "DA5") (pin "2") (pinfunction "REF_2") (pintype "passive"))
      (node (ref "R14") (pin "2") (pinfunction "2_2") (pintype "passive"))
      (node (ref "VT3") (pin "2") (pinfunction "2_2") (pintype "passive"))
    )
    (net (code "39") (name "Net-(DA6-CATHODE)") (class "Default")
      (node (ref "DA6") (pin "2") (pinfunction "CATHODE_2") (pintype "passive"))
      (node (ref "R13") (pin "1") (pinfunction "1_1") (pintype "passive"))
    )
    (net (code "40") (name "Net-(DA6-VO)") (class "Default")
      (node (ref "DA6") (pin "4") (pinfunction "VO_4") (pintype "passive"))
      (node (ref "R17") (pin "1") (pinfunction "1_1") (pintype "passive"))
      (node (ref "R20") (pin "1") (pinfunction "1_1") (pintype "passive"))
    )
    (net (code "41") (name "Net-(DA7-CATHODE)") (class "Default")
      (node (ref "DA7") (pin "1") (pinfunction "CATHODE_1") (pintype "passive"))
      (node (ref "R18") (pin "1") (pinfunction "1_1") (pintype "passive"))
      (node (ref "R21") (pin "1") (pinfunction "1_1") (pintype "passive"))
    )
    (net (code "42") (name "Net-(DA7-REF)") (class "Default")
      (node (ref "DA7") (pin "2") (pinfunction "REF_2") (pintype "passive"))
      (node (ref "R25") (pin "2") (pinfunction "2_2") (pintype "passive"))
      (node (ref "VT4") (pin "2") (pinfunction "2_2") (pintype "passive"))
    )
    (net (code "43") (name "Net-(DA8-CATHODE)") (class "Default")
      (node (ref "DA8") (pin "1") (pinfunction "CATHODE_1") (pintype "passive"))
      (node (ref "R19") (pin "1") (pinfunction "1_1") (pintype "passive"))
      (node (ref "R22") (pin "1") (pinfunction "1_1") (pintype "passive"))
    )
    (net (code "44") (name "Net-(DA8-REF)") (class "Default")
      (node (ref "DA8") (pin "2") (pinfunction "REF_2") (pintype "passive"))
      (node (ref "R26") (pin "2") (pinfunction "2_2") (pintype "passive"))
      (node (ref "VT5") (pin "2") (pinfunction "2_2") (pintype "passive"))
    )
    (net (code "45") (name "Net-(DA9-CATHODE)") (class "Default")
      (node (ref "DA9") (pin "2") (pinfunction "CATHODE_2") (pintype "passive"))
      (node (ref "R23") (pin "1") (pinfunction "1_1") (pintype "passive"))
    )
    (net (code "46") (name "Net-(DA9-VO)") (class "Default")
      (node (ref "DA9") (pin "4") (pinfunction "VO_4") (pintype "passive"))
      (node (ref "R28") (pin "1") (pinfunction "1_1") (pintype "passive"))
      (node (ref "R31") (pin "1") (pinfunction "1_1") (pintype "passive"))
    )
    (net (code "47") (name "Net-(DA10-CATHODE)") (class "Default")
      (node (ref "DA10") (pin "2") (pinfunction "CATHODE_2") (pintype "passive"))
      (node (ref "R24") (pin "1") (pinfunction "1_1") (pintype "passive"))
    )
    (net (code "48") (name "Net-(DA10-VO)") (class "Default")
      (node (ref "DA10") (pin "4") (pinfunction "VO_4") (pintype "passive"))
      (node (ref "R29") (pin "1") (pinfunction "1_1") (pintype "passive"))
      (node (ref "R32") (pin "1") (pinfunction "1_1") (pintype "passive"))
    )
    (net (code "49") (name "Net-(DA11-CATHODE)") (class "Default")
      (node (ref "DA11") (pin "1") (pinfunction "CATHODE_1") (pintype "passive"))
      (node (ref "R27") (pin "1") (pinfunction "1_1") (pintype "passive"))
      (node (ref "R30") (pin "1") (pinfunction "1_1") (pintype "passive"))
    )
    (net (code "50") (name "Net-(DA11-REF)") (class "Default")
      (node (ref "DA11") (pin "2") (pinfunction "REF_2") (pintype "passive"))
      (node (ref "R34") (pin "2") (pinfunction "2_2") (pintype "passive"))
      (node (ref "VT6") (pin "2") (pinfunction "2_2") (pintype "passive"))
    )
    (net (code "51") (name "Net-(DA12-CATHODE)") (class "Default")
      (node (ref "DA12") (pin "2") (pinfunction "CATHODE_2") (pintype "passive"))
      (node (ref "R33") (pin "1") (pinfunction "1_1") (pintype "passive"))
    )
    (net (code "52") (name "Net-(DA12-VO)") (class "Default")
      (node (ref "DA12") (pin "4") (pinfunction "VO_4") (pintype "passive"))
      (node (ref "R39") (pin "1") (pinfunction "1_1") (pintype "passive"))
      (node (ref "R40") (pin "1") (pinfunction "1_1") (pintype "passive"))
    )
    (net (code "53") (name "Net-(DA13-CATHODE)") (class "Default")
      (node (ref "DA13") (pin "1") (pinfunction "CATHODE_1") (pintype "passive"))
      (node (ref "R35") (pin "1") (pinfunction "1_1") (pintype "passive"))
      (node (ref "R37") (pin "1") (pinfunction "1_1") (pintype "passive"))
    )
    (net (code "54") (name "Net-(DA13-REF)") (class "Default")
      (node (ref "DA13") (pin "2") (pinfunction "REF_2") (pintype "passive"))
      (node (ref "R43") (pin "2") (pinfunction "2_2") (pintype "passive"))
      (node (ref "VT7") (pin "2") (pinfunction "2_2") (pintype "passive"))
    )
    (net (code "55") (name "Net-(DA14-CATHODE)") (class "Default")
      (node (ref "DA14") (pin "1") (pinfunction "CATHODE_1") (pintype "passive"))
      (node (ref "R36") (pin "1") (pinfunction "1_1") (pintype "passive"))
      (node (ref "R38") (pin "1") (pinfunction "1_1") (pintype "passive"))
    )
    (net (code "56") (name "Net-(DA14-REF)") (class "Default")
      (node (ref "DA14") (pin "2") (pinfunction "REF_2") (pintype "passive"))
      (node (ref "R44") (pin "2") (pinfunction "2_2") (pintype "passive"))
      (node (ref "VT8") (pin "2") (pinfunction "2_2") (pintype "passive"))
    )
    (net (code "57") (name "Net-(DA15-CATHODE)") (class "Default")
      (node (ref "DA15") (pin "2") (pinfunction "CATHODE_2") (pintype "passive"))
      (node (ref "R41") (pin "1") (pinfunction "1_1") (pintype "passive"))
    )
    (net (code "58") (name "Net-(DA15-VO)") (class "Default")
      (node (ref "DA15") (pin "4") (pinfunction "VO_4") (pintype "passive"))
      (node (ref "R46") (pin "1") (pinfunction "1_1") (pintype "passive"))
      (node (ref "R48") (pin "1") (pinfunction "1_1") (pintype "passive"))
    )
    (net (code "59") (name "Net-(DA16-CATHODE)") (class "Default")
      (node (ref "DA16") (pin "2") (pinfunction "CATHODE_2") (pintype "passive"))
      (node (ref "R42") (pin "1") (pinfunction "1_1") (pintype "passive"))
    )
    (net (code "60") (name "Net-(DA16-VO)") (class "Default")
      (node (ref "DA16") (pin "4") (pinfunction "VO_4") (pintype "passive"))
      (node (ref "R45") (pin "1") (pinfunction "1_1") (pintype "passive"))
      (node (ref "R47") (pin "1") (pinfunction "1_1") (pintype "passive"))
    )
    (net (code "61") (name "Net-(R3-Pad2)") (class "Default")
      (node (ref "R3") (pin "2") (pinfunction "2_2") (pintype "passive"))
      (node (ref "VT1") (pin "1") (pinfunction "1_1") (pintype "passive"))
    )
    (net (code "62") (name "Net-(R4-Pad2)") (class "Default")
      (node (ref "R4") (pin "2") (pinfunction "2_2") (pintype "passive"))
      (node (ref "VT2") (pin "1") (pinfunction "1_1") (pintype "passive"))
    )
    (net (code "63") (name "Net-(R8-Pad2)") (class "Default")
      (node (ref "R8") (pin "2") (pinfunction "2_2") (pintype "passive"))
      (node (ref "VT3") (pin "1") (pinfunction "1_1") (pintype "passive"))
    )
    (net (code "64") (name "Net-(R21-Pad2)") (class "Default")
      (node (ref "R21") (pin "2") (pinfunction "2_2") (pintype "passive"))
      (node (ref "VT4") (pin "1") (pinfunction "1_1") (pintype "passive"))
    )
    (net (code "65") (name "Net-(R22-Pad2)") (class "Default")
      (node (ref "R22") (pin "2") (pinfunction "2_2") (pintype "passive"))
      (node (ref "VT5") (pin "1") (pinfunction "1_1") (pintype "passive"))
    )
    (net (code "66") (name "Net-(R30-Pad2)") (class "Default")
      (node (ref "R30") (pin "2") (pinfunction "2_2") (pintype "passive"))
      (node (ref "VT6") (pin "1") (pinfunction "1_1") (pintype "passive"))
    )
    (net (code "67") (name "Net-(R37-Pad2)") (class "Default")
      (node (ref "R37") (pin "2") (pinfunction "2_2") (pintype "passive"))
      (node (ref "VT7") (pin "1") (pinfunction "1_1") (pintype "passive"))
    )
    (net (code "68") (name "Net-(R38-Pad2)") (class "Default")
      (node (ref "R38") (pin "2") (pinfunction "2_2") (pintype "passive"))
      (node (ref "VT8") (pin "1") (pinfunction "1_1") (pintype "passive"))
    )
    (net (code "69") (name "unconnected-(DA3-NC-Pad3)") (class "Default")
      (node (ref "DA3") (pin "3") (pinfunction "NC_3") (pintype "passive+no_connect"))
    )
    (net (code "70") (name "unconnected-(DA4-NC-Pad3)") (class "Default")
      (node (ref "DA4") (pin "3") (pinfunction "NC_3") (pintype "passive+no_connect"))
    )
    (net (code "71") (name "unconnected-(DA6-NC-Pad3)") (class "Default")
      (node (ref "DA6") (pin "3") (pinfunction "NC_3") (pintype "passive+no_connect"))
    )
    (net (code "72") (name "unconnected-(DA9-NC-Pad3)") (class "Default")
      (node (ref "DA9") (pin "3") (pinfunction "NC_3") (pintype "passive+no_connect"))
    )
    (net (code "73") (name "unconnected-(DA10-NC-Pad3)") (class "Default")
      (node (ref "DA10") (pin "3") (pinfunction "NC_3") (pintype "passive+no_connect"))
    )
    (net (code "74") (name "unconnected-(DA12-NC-Pad3)") (class "Default")
      (node (ref "DA12") (pin "3") (pinfunction "NC_3") (pintype "passive+no_connect"))
    )
    (net (code "75") (name "unconnected-(DA15-NC-Pad3)") (class "Default")
      (node (ref "DA15") (pin "3") (pinfunction "NC_3") (pintype "passive+no_connect"))
    )
    (net (code "76") (name "unconnected-(DA16-NC-Pad3)") (class "Default")
      (node (ref "DA16") (pin "3") (pinfunction "NC_3") (pintype "passive+no_connect"))
    )
  )
)
